# RAM_final_rev02.net
KiCad netlist of a schematic drawn in EAGLE
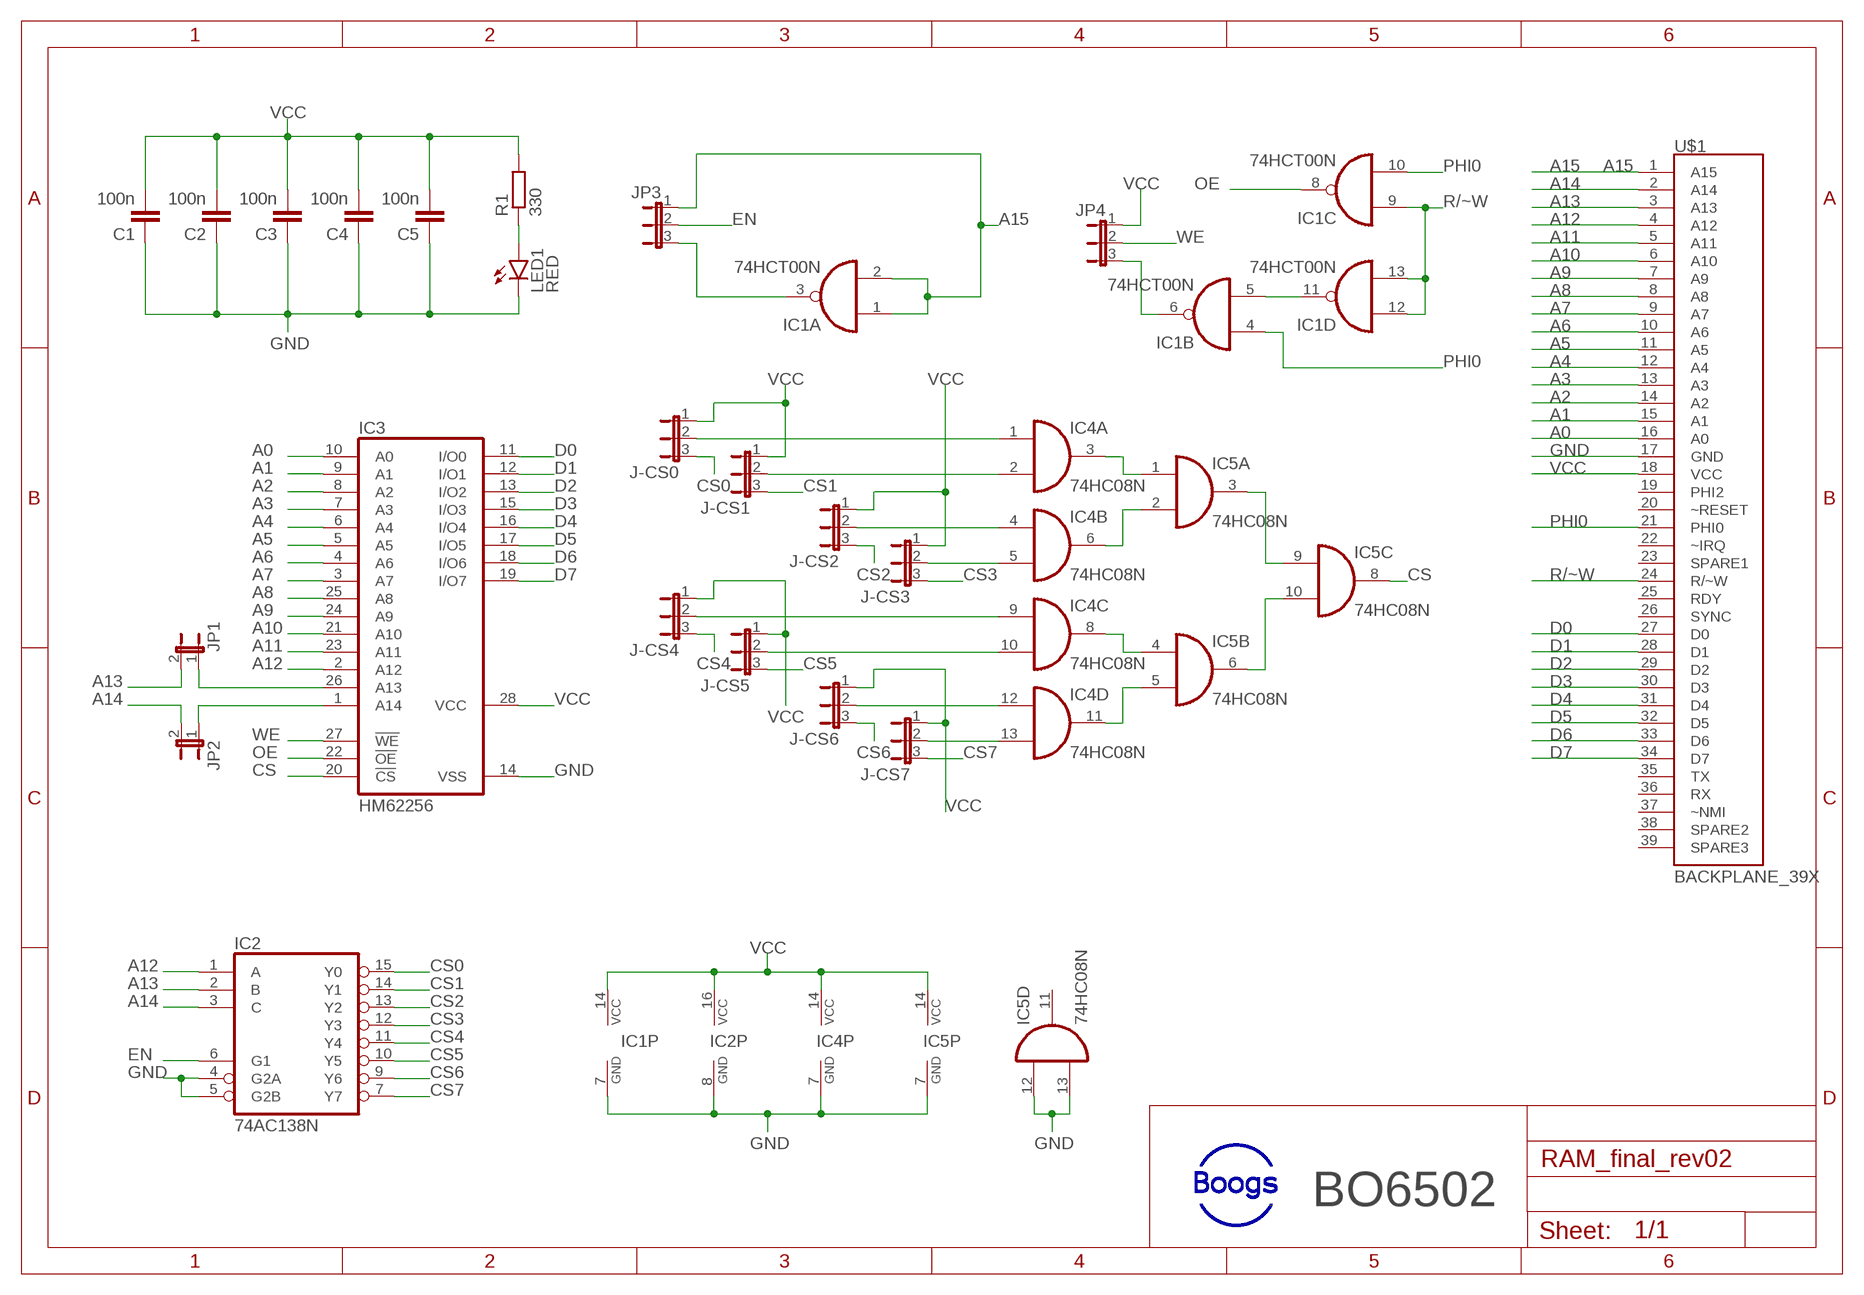
[diagram p0: schematic, sheet 1]

(export (version "E")
  (design (tool "Eeschema 10.0.6"))
  (components
    (comp (ref "C1")
      (value "100n")
      (footprint "eagle-import:C025-025X050")
      (libsource (lib "eagle-import") (part "C-EU025-025X050"))
    )
    (comp (ref "C2")
      (value "100n")
      (footprint "eagle-import:C025-025X050")
      (libsource (lib "eagle-import") (part "C-EU025-025X050"))
    )
    (comp (ref "C3")
      (value "100n")
      (footprint "eagle-import:C025-025X050")
      (libsource (lib "eagle-import") (part "C-EU025-025X050"))
    )
    (comp (ref "C4")
      (value "100n")
      (footprint "eagle-import:C025-025X050")
      (libsource (lib "eagle-import") (part "C-EU025-025X050"))
    )
    (comp (ref "C5")
      (value "100n")
      (footprint "eagle-import:C025-025X050")
      (libsource (lib "eagle-import") (part "C-EU025-025X050"))
    )
    (comp (ref "IC1")
      (value "74HCT00N")
      (footprint "eagle-import:DIL14")
      (libsource (lib "eagle-import") (part "7400NHCT"))
    )
    (comp (ref "IC2")
      (value "74AC138N")
      (footprint "eagle-import:DIL16")
      (libsource (lib "eagle-import") (part "74138NAC"))
    )
    (comp (ref "IC3")
      (value "HM62256")
      (footprint "eagle-import:DIL28-6")
      (libsource (lib "eagle-import") (part "62256P"))
    )
    (comp (ref "IC4")
      (value "74HC08N")
      (footprint "eagle-import:DIL14")
      (libsource (lib "eagle-import") (part "7408NHC"))
    )
    (comp (ref "IC5")
      (value "74HC08N")
      (footprint "eagle-import:DIL14")
      (libsource (lib "eagle-import") (part "7408NHC"))
    )
    (comp (ref "J-CS0")
      (value "J-CS0")
      (footprint "eagle-import:JP2")
      (libsource (lib "eagle-import") (part "JP2E"))
    )
    (comp (ref "J-CS1")
      (value "J-CS1")
      (footprint "eagle-import:JP2")
      (libsource (lib "eagle-import") (part "JP2E"))
    )
    (comp (ref "J-CS2")
      (value "J-CS2")
      (footprint "eagle-import:JP2")
      (libsource (lib "eagle-import") (part "JP2E"))
    )
    (comp (ref "J-CS3")
      (value "J-CS3")
      (footprint "eagle-import:JP2")
      (libsource (lib "eagle-import") (part "JP2E"))
    )
    (comp (ref "J-CS4")
      (value "J-CS4")
      (footprint "eagle-import:JP2")
      (libsource (lib "eagle-import") (part "JP2E"))
    )
    (comp (ref "J-CS5")
      (value "J-CS5")
      (footprint "eagle-import:JP2")
      (libsource (lib "eagle-import") (part "JP2E"))
    )
    (comp (ref "J-CS6")
      (value "J-CS6")
      (footprint "eagle-import:JP2")
      (libsource (lib "eagle-import") (part "JP2E"))
    )
    (comp (ref "J-CS7")
      (value "J-CS7")
      (footprint "eagle-import:JP2")
      (libsource (lib "eagle-import") (part "JP2E"))
    )
    (comp (ref "JP1")
      (value "JP1")
      (footprint "eagle-import:JP1")
      (libsource (lib "eagle-import") (part "JP1E"))
    )
    (comp (ref "JP2")
      (value "JP2")
      (footprint "eagle-import:JP1")
      (libsource (lib "eagle-import") (part "JP1E"))
    )
    (comp (ref "JP3")
      (value "JP3")
      (footprint "eagle-import:JP2")
      (libsource (lib "eagle-import") (part "JP2E"))
    )
    (comp (ref "JP4")
      (value "JP4")
      (footprint "eagle-import:JP2")
      (libsource (lib "eagle-import") (part "JP2E"))
    )
    (comp (ref "LED1")
      (value "RED")
      (footprint "eagle-import:LED5MM")
      (libsource (lib "eagle-import") (part "LED5MM"))
    )
    (comp (ref "R1")
      (value "330")
      (footprint "eagle-import:0207_10")
      (libsource (lib "eagle-import") (part "R-EU_0207/10"))
    )
    (comp (ref "U$1")
      (value "BACKPLANE_39X")
      (footprint "eagle-import:BP_39X")
      (fields (field (name "A15") "A15"))
      (libsource (lib "eagle-import") (part "BACKPLANE_39X"))
    )
  )
  (nets
    (net (code "1") (name "/A0") (class "Default")
      (node (ref "IC3") (pin "10") (pinfunction "A0_10") (pintype "input"))
      (node (ref "U$1") (pin "16") (pinfunction "A0_16") (pintype "bidirectional"))
    )
    (net (code "2") (name "/A1") (class "Default")
      (node (ref "IC3") (pin "9") (pinfunction "A1_9") (pintype "input"))
      (node (ref "U$1") (pin "15") (pinfunction "A1_15") (pintype "bidirectional"))
    )
    (net (code "3") (name "/A2") (class "Default")
      (node (ref "IC3") (pin "8") (pinfunction "A2_8") (pintype "input"))
      (node (ref "U$1") (pin "14") (pinfunction "A2_14") (pintype "bidirectional"))
    )
    (net (code "4") (name "/A3") (class "Default")
      (node (ref "IC3") (pin "7") (pinfunction "A3_7") (pintype "input"))
      (node (ref "U$1") (pin "13") (pinfunction "A3_13") (pintype "bidirectional"))
    )
    (net (code "5") (name "/A4") (class "Default")
      (node (ref "IC3") (pin "6") (pinfunction "A4_6") (pintype "input"))
      (node (ref "U$1") (pin "12") (pinfunction "A4_12") (pintype "bidirectional"))
    )
    (net (code "6") (name "/A5") (class "Default")
      (node (ref "IC3") (pin "5") (pinfunction "A5_5") (pintype "input"))
      (node (ref "U$1") (pin "11") (pinfunction "A5_11") (pintype "bidirectional"))
    )
    (net (code "7") (name "/A6") (class "Default")
      (node (ref "IC3") (pin "4") (pinfunction "A6_4") (pintype "input"))
      (node (ref "U$1") (pin "10") (pinfunction "A6_10") (pintype "bidirectional"))
    )
    (net (code "8") (name "/A7") (class "Default")
      (node (ref "IC3") (pin "3") (pinfunction "A7_3") (pintype "input"))
      (node (ref "U$1") (pin "9") (pinfunction "A7_9") (pintype "bidirectional"))
    )
    (net (code "9") (name "/A8") (class "Default")
      (node (ref "IC3") (pin "25") (pinfunction "A8_25") (pintype "input"))
      (node (ref "U$1") (pin "8") (pinfunction "A8_8") (pintype "bidirectional"))
    )
    (net (code "10") (name "/A9") (class "Default")
      (node (ref "IC3") (pin "24") (pinfunction "A9_24") (pintype "input"))
      (node (ref "U$1") (pin "7") (pinfunction "A9_7") (pintype "bidirectional"))
    )
    (net (code "11") (name "/A10") (class "Default")
      (node (ref "IC3") (pin "21") (pinfunction "A10_21") (pintype "input"))
      (node (ref "U$1") (pin "6") (pinfunction "A10_6") (pintype "bidirectional"))
    )
    (net (code "12") (name "/A11") (class "Default")
      (node (ref "IC3") (pin "23") (pinfunction "A11_23") (pintype "input"))
      (node (ref "U$1") (pin "5") (pinfunction "A11_5") (pintype "bidirectional"))
    )
    (net (code "13") (name "/A12") (class "Default")
      (node (ref "IC2") (pin "1") (pinfunction "A_1") (pintype "input"))
      (node (ref "IC3") (pin "2") (pinfunction "A12_2") (pintype "input"))
      (node (ref "U$1") (pin "4") (pinfunction "A12_4") (pintype "bidirectional"))
    )
    (net (code "14") (name "/A13") (class "Default")
      (node (ref "IC2") (pin "2") (pinfunction "B_2") (pintype "input"))
      (node (ref "JP1") (pin "2") (pinfunction "2_2") (pintype "passive"))
      (node (ref "U$1") (pin "3") (pinfunction "A13_3") (pintype "bidirectional"))
    )
    (net (code "15") (name "/A14") (class "Default")
      (node (ref "IC2") (pin "3") (pinfunction "C_3") (pintype "input"))
      (node (ref "JP2") (pin "2") (pinfunction "2_2") (pintype "passive"))
      (node (ref "U$1") (pin "2") (pinfunction "A14_2") (pintype "bidirectional"))
    )
    (net (code "16") (name "/A15") (class "Default")
      (node (ref "IC1") (pin "1") (pinfunction "I0_1") (pintype "input"))
      (node (ref "IC1") (pin "2") (pinfunction "I1_2") (pintype "input"))
      (node (ref "JP3") (pin "1") (pinfunction "1_1") (pintype "passive"))
      (node (ref "U$1") (pin "1") (pinfunction "A15_1") (pintype "bidirectional"))
    )
    (net (code "17") (name "/CS") (class "Default")
      (node (ref "IC3") (pin "20") (pinfunction "~{CS}_20") (pintype "input"))
      (node (ref "IC5") (pin "8") (pinfunction "O_8") (pintype "output"))
    )
    (net (code "18") (name "/CS0") (class "Default")
      (node (ref "IC2") (pin "15") (pinfunction "Y0_15") (pintype "output"))
      (node (ref "J-CS0") (pin "3") (pinfunction "3_3") (pintype "passive"))
    )
    (net (code "19") (name "/CS1") (class "Default")
      (node (ref "IC2") (pin "14") (pinfunction "Y1_14") (pintype "output"))
      (node (ref "J-CS1") (pin "3") (pinfunction "3_3") (pintype "passive"))
    )
    (net (code "20") (name "/CS2") (class "Default")
      (node (ref "IC2") (pin "13") (pinfunction "Y2_13") (pintype "output"))
      (node (ref "J-CS2") (pin "3") (pinfunction "3_3") (pintype "passive"))
    )
    (net (code "21") (name "/CS3") (class "Default")
      (node (ref "IC2") (pin "12") (pinfunction "Y3_12") (pintype "output"))
      (node (ref "J-CS3") (pin "3") (pinfunction "3_3") (pintype "passive"))
    )
    (net (code "22") (name "/CS4") (class "Default")
      (node (ref "IC2") (pin "11") (pinfunction "Y4_11") (pintype "output"))
      (node (ref "J-CS4") (pin "3") (pinfunction "3_3") (pintype "passive"))
    )
    (net (code "23") (name "/CS5") (class "Default")
      (node (ref "IC2") (pin "10") (pinfunction "Y5_10") (pintype "output"))
      (node (ref "J-CS5") (pin "3") (pinfunction "3_3") (pintype "passive"))
    )
    (net (code "24") (name "/CS6") (class "Default")
      (node (ref "IC2") (pin "9") (pinfunction "Y6_9") (pintype "output"))
      (node (ref "J-CS6") (pin "3") (pinfunction "3_3") (pintype "passive"))
    )
    (net (code "25") (name "/CS7") (class "Default")
      (node (ref "IC2") (pin "7") (pinfunction "Y7_7") (pintype "output"))
      (node (ref "J-CS7") (pin "3") (pinfunction "3_3") (pintype "passive"))
    )
    (net (code "26") (name "/D0") (class "Default")
      (node (ref "IC3") (pin "11") (pinfunction "I/O0_11") (pintype "bidirectional"))
      (node (ref "U$1") (pin "27") (pinfunction "D0_27") (pintype "bidirectional"))
    )
    (net (code "27") (name "/D1") (class "Default")
      (node (ref "IC3") (pin "12") (pinfunction "I/O1_12") (pintype "bidirectional"))
      (node (ref "U$1") (pin "28") (pinfunction "D1_28") (pintype "bidirectional"))
    )
    (net (code "28") (name "/D2") (class "Default")
      (node (ref "IC3") (pin "13") (pinfunction "I/O2_13") (pintype "bidirectional"))
      (node (ref "U$1") (pin "29") (pinfunction "D2_29") (pintype "bidirectional"))
    )
    (net (code "29") (name "/D3") (class "Default")
      (node (ref "IC3") (pin "15") (pinfunction "I/O3_15") (pintype "bidirectional"))
      (node (ref "U$1") (pin "30") (pinfunction "D3_30") (pintype "bidirectional"))
    )
    (net (code "30") (name "/D4") (class "Default")
      (node (ref "IC3") (pin "16") (pinfunction "I/O4_16") (pintype "bidirectional"))
      (node (ref "U$1") (pin "31") (pinfunction "D4_31") (pintype "bidirectional"))
    )
    (net (code "31") (name "/D5") (class "Default")
      (node (ref "IC3") (pin "17") (pinfunction "I/O5_17") (pintype "bidirectional"))
      (node (ref "U$1") (pin "32") (pinfunction "D5_32") (pintype "bidirectional"))
    )
    (net (code "32") (name "/D6") (class "Default")
      (node (ref "IC3") (pin "18") (pinfunction "I/O6_18") (pintype "bidirectional"))
      (node (ref "U$1") (pin "33") (pinfunction "D6_33") (pintype "bidirectional"))
    )
    (net (code "33") (name "/D7") (class "Default")
      (node (ref "IC3") (pin "19") (pinfunction "I/O7_19") (pintype "bidirectional"))
      (node (ref "U$1") (pin "34") (pinfunction "D7_34") (pintype "bidirectional"))
    )
    (net (code "34") (name "/EN") (class "Default")
      (node (ref "IC2") (pin "6") (pinfunction "G1_6") (pintype "input"))
      (node (ref "JP3") (pin "2") (pinfunction "2_2") (pintype "passive"))
    )
    (net (code "35") (name "/GND") (class "Default")
      (node (ref "C1") (pin "1") (pinfunction "1_1") (pintype "passive"))
      (node (ref "C2") (pin "1") (pinfunction "1_1") (pintype "passive"))
      (node (ref "C3") (pin "1") (pinfunction "1_1") (pintype "passive"))
      (node (ref "C4") (pin "1") (pinfunction "1_1") (pintype "passive"))
      (node (ref "C5") (pin "1") (pinfunction "1_1") (pintype "passive"))
      (node (ref "IC1") (pin "7") (pinfunction "GND_7") (pintype "power_in"))
      (node (ref "IC2") (pin "4") (pinfunction "G2A_4") (pintype "input"))
      (node (ref "IC2") (pin "5") (pinfunction "G2B_5") (pintype "input"))
      (node (ref "IC2") (pin "8") (pinfunction "GND_8") (pintype "power_in"))
      (node (ref "IC3") (pin "14") (pinfunction "VSS_14") (pintype "power_in"))
      (node (ref "IC4") (pin "7") (pinfunction "GND_7") (pintype "power_in"))
      (node (ref "IC5") (pin "12") (pinfunction "I0_12") (pintype "input"))
      (node (ref "IC5") (pin "13") (pinfunction "I1_13") (pintype "input"))
      (node (ref "IC5") (pin "7") (pinfunction "GND_7") (pintype "power_in"))
      (node (ref "LED1") (pin "K") (pinfunction "C_K") (pintype "passive"))
      (node (ref "U$1") (pin "17") (pinfunction "GND_17") (pintype "bidirectional"))
    )
    (net (code "36") (name "/OE") (class "Default")
      (node (ref "IC1") (pin "8") (pinfunction "O_8") (pintype "output"))
      (node (ref "IC3") (pin "22") (pinfunction "~{OE}_22") (pintype "input"))
    )
    (net (code "37") (name "/PHI0") (class "Default")
      (node (ref "IC1") (pin "10") (pinfunction "I1_10") (pintype "input"))
      (node (ref "IC1") (pin "4") (pinfunction "I0_4") (pintype "input"))
      (node (ref "U$1") (pin "21") (pinfunction "PHI0_21") (pintype "bidirectional"))
    )
    (net (code "38") (name "/R{slash}~{W}") (class "Default")
      (node (ref "IC1") (pin "12") (pinfunction "I0_12") (pintype "input"))
      (node (ref "IC1") (pin "13") (pinfunction "I1_13") (pintype "input"))
      (node (ref "IC1") (pin "9") (pinfunction "I0_9") (pintype "input"))
      (node (ref "U$1") (pin "24") (pinfunction "R/~{W}_24") (pintype "bidirectional"))
    )
    (net (code "39") (name "/VCC") (class "Default")
      (node (ref "C1") (pin "2") (pinfunction "2_2") (pintype "passive"))
      (node (ref "C2") (pin "2") (pinfunction "2_2") (pintype "passive"))
      (node (ref "C3") (pin "2") (pinfunction "2_2") (pintype "passive"))
      (node (ref "C4") (pin "2") (pinfunction "2_2") (pintype "passive"))
      (node (ref "C5") (pin "2") (pinfunction "2_2") (pintype "passive"))
      (node (ref "IC1") (pin "14") (pinfunction "VCC_14") (pintype "power_in"))
      (node (ref "IC2") (pin "16") (pinfunction "VCC_16") (pintype "power_in"))
      (node (ref "IC3") (pin "28") (pinfunction "VCC_28") (pintype "power_in"))
      (node (ref "IC4") (pin "14") (pinfunction "VCC_14") (pintype "power_in"))
      (node (ref "IC5") (pin "14") (pinfunction "VCC_14") (pintype "power_in"))
      (node (ref "J-CS0") (pin "1") (pinfunction "1_1") (pintype "passive"))
      (node (ref "J-CS1") (pin "1") (pinfunction "1_1") (pintype "passive"))
      (node (ref "J-CS2") (pin "1") (pinfunction "1_1") (pintype "passive"))
      (node (ref "J-CS3") (pin "1") (pinfunction "1_1") (pintype "passive"))
      (node (ref "J-CS4") (pin "1") (pinfunction "1_1") (pintype "passive"))
      (node (ref "J-CS5") (pin "1") (pinfunction "1_1") (pintype "passive"))
      (node (ref "J-CS6") (pin "1") (pinfunction "1_1") (pintype "passive"))
      (node (ref "J-CS7") (pin "1") (pinfunction "1_1") (pintype "passive"))
      (node (ref "JP4") (pin "1") (pinfunction "1_1") (pintype "passive"))
      (node (ref "R1") (pin "2") (pinfunction "2_2") (pintype "passive"))
      (node (ref "U$1") (pin "18") (pinfunction "VCC_18") (pintype "bidirectional"))
    )
    (net (code "40") (name "/WE") (class "Default")
      (node (ref "IC3") (pin "27") (pinfunction "~{WE}_27") (pintype "input"))
      (node (ref "JP4") (pin "2") (pinfunction "2_2") (pintype "passive"))
    )
    (net (code "41") (name "Net-(IC1A-O)") (class "Default")
      (node (ref "IC1") (pin "3") (pinfunction "O_3") (pintype "output"))
      (node (ref "JP3") (pin "3") (pinfunction "3_3") (pintype "passive"))
    )
    (net (code "42") (name "Net-(IC1B-I1)") (class "Default")
      (node (ref "IC1") (pin "11") (pinfunction "O_11") (pintype "output"))
      (node (ref "IC1") (pin "5") (pinfunction "I1_5") (pintype "input"))
    )
    (net (code "43") (name "Net-(IC1B-O)") (class "Default")
      (node (ref "IC1") (pin "6") (pinfunction "O_6") (pintype "output"))
      (node (ref "JP4") (pin "3") (pinfunction "3_3") (pintype "passive"))
    )
    (net (code "44") (name "Net-(IC3-A13)") (class "Default")
      (node (ref "IC3") (pin "26") (pinfunction "A13_26") (pintype "input"))
      (node (ref "JP1") (pin "1") (pinfunction "1_1") (pintype "passive"))
    )
    (net (code "45") (name "Net-(IC3-A14)") (class "Default")
      (node (ref "IC3") (pin "1") (pinfunction "A14_1") (pintype "input"))
      (node (ref "JP2") (pin "1") (pinfunction "1_1") (pintype "passive"))
    )
    (net (code "46") (name "Net-(IC4A-I0)") (class "Default")
      (node (ref "IC4") (pin "1") (pinfunction "I0_1") (pintype "input"))
      (node (ref "J-CS0") (pin "2") (pinfunction "2_2") (pintype "passive"))
    )
    (net (code "47") (name "Net-(IC4A-I1)") (class "Default")
      (node (ref "IC4") (pin "2") (pinfunction "I1_2") (pintype "input"))
      (node (ref "J-CS1") (pin "2") (pinfunction "2_2") (pintype "passive"))
    )
    (net (code "48") (name "Net-(IC4A-O)") (class "Default")
      (node (ref "IC4") (pin "3") (pinfunction "O_3") (pintype "output"))
      (node (ref "IC5") (pin "1") (pinfunction "I0_1") (pintype "input"))
    )
    (net (code "49") (name "Net-(IC4B-I0)") (class "Default")
      (node (ref "IC4") (pin "4") (pinfunction "I0_4") (pintype "input"))
      (node (ref "J-CS2") (pin "2") (pinfunction "2_2") (pintype "passive"))
    )
    (net (code "50") (name "Net-(IC4B-I1)") (class "Default")
      (node (ref "IC4") (pin "5") (pinfunction "I1_5") (pintype "input"))
      (node (ref "J-CS3") (pin "2") (pinfunction "2_2") (pintype "passive"))
    )
    (net (code "51") (name "Net-(IC4B-O)") (class "Default")
      (node (ref "IC4") (pin "6") (pinfunction "O_6") (pintype "output"))
      (node (ref "IC5") (pin "2") (pinfunction "I1_2") (pintype "input"))
    )
    (net (code "52") (name "Net-(IC4C-I0)") (class "Default")
      (node (ref "IC4") (pin "9") (pinfunction "I0_9") (pintype "input"))
      (node (ref "J-CS4") (pin "2") (pinfunction "2_2") (pintype "passive"))
    )
    (net (code "53") (name "Net-(IC4C-I1)") (class "Default")
      (node (ref "IC4") (pin "10") (pinfunction "I1_10") (pintype "input"))
      (node (ref "J-CS5") (pin "2") (pinfunction "2_2") (pintype "passive"))
    )
    (net (code "54") (name "Net-(IC4C-O)") (class "Default")
      (node (ref "IC4") (pin "8") (pinfunction "O_8") (pintype "output"))
      (node (ref "IC5") (pin "4") (pinfunction "I0_4") (pintype "input"))
    )
    (net (code "55") (name "Net-(IC4D-I0)") (class "Default")
      (node (ref "IC4") (pin "12") (pinfunction "I0_12") (pintype "input"))
      (node (ref "J-CS6") (pin "2") (pinfunction "2_2") (pintype "passive"))
    )
    (net (code "56") (name "Net-(IC4D-I1)") (class "Default")
      (node (ref "IC4") (pin "13") (pinfunction "I1_13") (pintype "input"))
      (node (ref "J-CS7") (pin "2") (pinfunction "2_2") (pintype "passive"))
    )
    (net (code "57") (name "Net-(IC4D-O)") (class "Default")
      (node (ref "IC4") (pin "11") (pinfunction "O_11") (pintype "output"))
      (node (ref "IC5") (pin "5") (pinfunction "I1_5") (pintype "input"))
    )
    (net (code "58") (name "Net-(IC5A-O)") (class "Default")
      (node (ref "IC5") (pin "3") (pinfunction "O_3") (pintype "output"))
      (node (ref "IC5") (pin "9") (pinfunction "I0_9") (pintype "input"))
    )
    (net (code "59") (name "Net-(IC5B-O)") (class "Default")
      (node (ref "IC5") (pin "10") (pinfunction "I1_10") (pintype "input"))
      (node (ref "IC5") (pin "6") (pinfunction "O_6") (pintype "output"))
    )
    (net (code "60") (name "Net-(LED1-PadA)") (class "Default")
      (node (ref "LED1") (pin "A") (pinfunction "A_A") (pintype "passive"))
      (node (ref "R1") (pin "1") (pinfunction "1_1") (pintype "passive"))
    )
    (net (code "61") (name "unconnected-(IC5D-O-Pad11)") (class "Default")
      (node (ref "IC5") (pin "11") (pinfunction "O_11") (pintype "output"))
    )
    (net (code "62") (name "unconnected-(U$1-PHI2-Pad19)") (class "Default")
      (node (ref "U$1") (pin "19") (pinfunction "PHI2_19") (pintype "bidirectional"))
    )
    (net (code "63") (name "unconnected-(U$1-RDY-Pad25)") (class "Default")
      (node (ref "U$1") (pin "25") (pinfunction "RDY_25") (pintype "bidirectional"))
    )
    (net (code "64") (name "unconnected-(U$1-RX-Pad36)") (class "Default")
      (node (ref "U$1") (pin "36") (pinfunction "RX_36") (pintype "bidirectional"))
    )
    (net (code "65") (name "unconnected-(U$1-SPARE1-Pad23)") (class "Default")
      (node (ref "U$1") (pin "23") (pinfunction "SPARE1_23") (pintype "bidirectional"))
    )
    (net (code "66") (name "unconnected-(U$1-SPARE2-Pad38)") (class "Default")
      (node (ref "U$1") (pin "38") (pinfunction "SPARE2_38") (pintype "bidirectional"))
    )
    (net (code "67") (name "unconnected-(U$1-SPARE3-Pad39)") (class "Default")
      (node (ref "U$1") (pin "39") (pinfunction "SPARE3_39") (pintype "bidirectional"))
    )
    (net (code "68") (name "unconnected-(U$1-SYNC-Pad26)") (class "Default")
      (node (ref "U$1") (pin "26") (pinfunction "SYNC_26") (pintype "bidirectional"))
    )
    (net (code "69") (name "unconnected-(U$1-TX-Pad35)") (class "Default")
      (node (ref "U$1") (pin "35") (pinfunction "TX_35") (pintype "bidirectional"))
    )
    (net (code "70") (name "unconnected-(U$1-~{IRQ}-Pad22)") (class "Default")
      (node (ref "U$1") (pin "22") (pinfunction "~{IRQ}_22") (pintype "bidirectional"))
    )
    (net (code "71") (name "unconnected-(U$1-~{NMI}-Pad37)") (class "Default")
      (node (ref "U$1") (pin "37") (pinfunction "~{NMI}_37") (pintype "bidirectional"))
    )
    (net (code "72") (name "unconnected-(U$1-~{RESET}-Pad20)") (class "Default")
      (node (ref "U$1") (pin "20") (pinfunction "~{RESET}_20") (pintype "bidirectional"))
    )
  )
)
